# USB_charger.net
KiCad netlist of a schematic drawn in Altium Designer
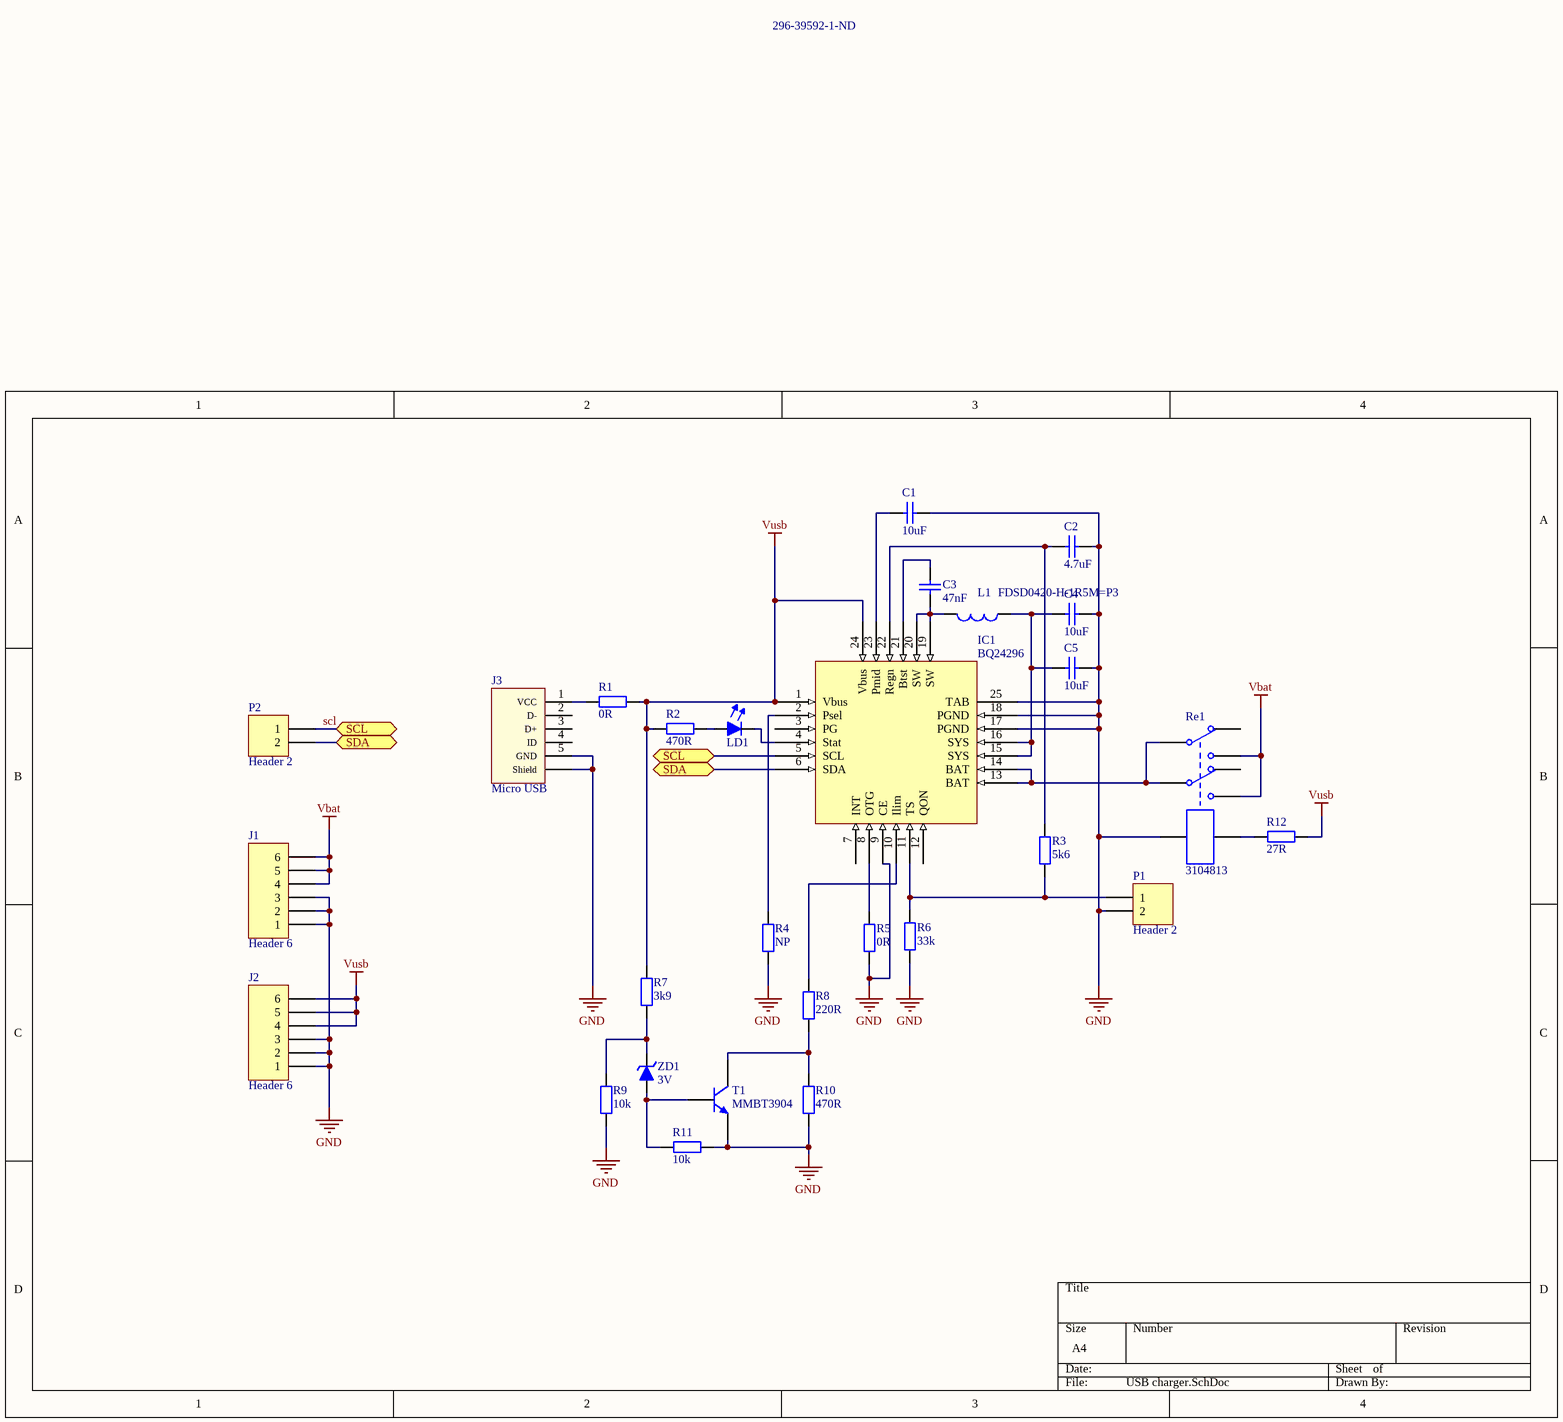
[diagram p0: USB charger.SchDoc]

(export (version "E")
  (design (tool "Eeschema 10.0.6"))
  (components
    (comp (ref "C1")
      (value "10uF")
      (footprint "0805 CAP")
      (description "Capacitor")
      (fields (field (name "VOLTAGE") "10V"))
      (libsource (lib "IKSOR_LIB_main") (part "Capacitor NP"))
    )
    (comp (ref "C2")
      (value "4.7uF")
      (footprint "0805 CAP")
      (description "Capacitor")
      (fields (field (name "VOLTAGE") "10V"))
      (libsource (lib "IKSOR_LIB_main") (part "Capacitor NP"))
    )
    (comp (ref "C3")
      (value "47nF")
      (footprint "0603 cap")
      (description "Capacitor")
      (fields (field (name "VOLTAGE") "10V"))
      (libsource (lib "IKSOR_LIB_main") (part "Capacitor NP"))
    )
    (comp (ref "C4")
      (value "10uF")
      (footprint "0805 CAP")
      (description "Capacitor")
      (fields (field (name "VOLTAGE") "10V"))
      (libsource (lib "IKSOR_LIB_main") (part "Capacitor NP"))
    )
    (comp (ref "C5")
      (value "10uF")
      (footprint "0805 CAP")
      (description "Capacitor")
      (fields (field (name "VOLTAGE") "10V"))
      (libsource (lib "IKSOR_LIB_main") (part "Capacitor NP"))
    )
    (comp (ref "IC1")
      (value "BQ24296")
      (footprint "QFN4x4")
      (description "Battery charger")
      (fields (field (name "SUPPLIER PART NUMBER 1") "296-39592-1-ND"))
      (libsource (lib "IKSOR_LIB_main") (part "BQ24296"))
    )
    (comp (ref "J1")
      (value "Header 6")
      (footprint "HDR1X6")
      (description "Header, 6-Pin")
      (fields (field (name "PUBLISHER") "Altium Limited"))
      (libsource (lib "Miscellaneous Connectors") (part "Header 6"))
    )
    (comp (ref "J2")
      (value "Header 6")
      (footprint "HDR1X6")
      (description "Header, 6-Pin")
      (fields (field (name "PUBLISHER") "Altium Limited"))
      (libsource (lib "Miscellaneous Connectors") (part "Header 6"))
    )
    (comp (ref "J3")
      (value "Micro USB")
      (footprint "629105150521")
      (description "Micro USB 2.0 SMT Type B Horizontal 5 Contacts High Current WR-COM")
      (fields (field (name "PART NUMBER") "629105150521") (field (name "PUBLISHER") "Wurth Elektronik"))
      (libsource (lib "ALTIUM-WR-COM-rev17a") (part "629105150521"))
    )
    (comp (ref "L1")
      (value "FDSD0420-H-1R5M=P3")
      (footprint "FDSD0420-H")
      (description "Single coil")
      (fields (field (name "Comment") "Inductor FDSD0420"))
      (libsource (lib "IKSOR_LIB_main") (part "Inductor"))
    )
    (comp (ref "LD1")
      (value "LED diode")
      (footprint "LED_0603")
      (description "LED")
      (libsource (lib "IKSOR_LIB_main") (part "LED diode"))
    )
    (comp (ref "P1")
      (value "Header 2")
      (footprint "HDR1X2")
      (description "Header, 2-Pin")
      (fields (field (name "PUBLISHER") "Altium Limited"))
      (libsource (lib "") (part "Header 2_1"))
    )
    (comp (ref "P2")
      (value "Header 2")
      (footprint "HDR1X2")
      (description "Header, 2-Pin")
      (fields (field (name "PUBLISHER") "Altium Limited"))
      (libsource (lib "Miscellaneous Connectors") (part "Header 2"))
    )
    (comp (ref "R1")
      (value "0R")
      (footprint "0805 RES")
      (description "Resistor SMD")
      (fields (field (name "Comment") "Resistor generic"))
      (libsource (lib "IKSOR_LIB_main") (part "Resistor"))
    )
    (comp (ref "R2")
      (value "470R")
      (footprint "0603 RES")
      (description "Resistor SMD")
      (fields (field (name "Comment") "Resistor generic"))
      (libsource (lib "IKSOR_LIB_main") (part "Resistor"))
    )
    (comp (ref "R3")
      (value "5k6")
      (footprint "0603 RES")
      (description "Resistor SMD")
      (fields (field (name "Comment") "Resistor generic"))
      (libsource (lib "IKSOR_LIB_main") (part "Resistor"))
    )
    (comp (ref "R4")
      (value "NP")
      (footprint "0603 RES")
      (description "Resistor SMD")
      (fields (field (name "Comment") "Resistor generic"))
      (libsource (lib "IKSOR_LIB_main") (part "Resistor"))
    )
    (comp (ref "R5")
      (value "0R")
      (footprint "0603 RES")
      (description "Resistor SMD")
      (fields (field (name "Comment") "Resistor generic"))
      (libsource (lib "IKSOR_LIB_main") (part "Resistor"))
    )
    (comp (ref "R6")
      (value "33k")
      (footprint "0603 RES")
      (description "Resistor SMD")
      (fields (field (name "Comment") "Resistor generic"))
      (libsource (lib "IKSOR_LIB_main") (part "Resistor"))
    )
    (comp (ref "R7")
      (value "3k9")
      (footprint "0603 RES")
      (description "Resistor SMD")
      (fields (field (name "Comment") "Resistor generic"))
      (libsource (lib "IKSOR_LIB_main") (part "Resistor"))
    )
    (comp (ref "R8")
      (value "220R")
      (footprint "0603 RES")
      (description "Resistor SMD")
      (fields (field (name "Comment") "Resistor generic"))
      (libsource (lib "IKSOR_LIB_main") (part "Resistor"))
    )
    (comp (ref "R9")
      (value "10k")
      (footprint "0603 RES")
      (description "Resistor SMD")
      (fields (field (name "Comment") "Resistor generic"))
      (libsource (lib "IKSOR_LIB_main") (part "Resistor"))
    )
    (comp (ref "R10")
      (value "470R")
      (footprint "0603 RES")
      (description "Resistor SMD")
      (fields (field (name "Comment") "Resistor generic"))
      (libsource (lib "IKSOR_LIB_main") (part "Resistor"))
    )
    (comp (ref "R11")
      (value "10k")
      (footprint "0603 RES")
      (description "Resistor SMD")
      (fields (field (name "Comment") "Resistor generic"))
      (libsource (lib "IKSOR_LIB_main") (part "Resistor"))
    )
    (comp (ref "R12")
      (value "27R")
      (footprint "0603 RES")
      (description "Resistor SMD")
      (fields (field (name "Comment") "Resistor generic"))
      (libsource (lib "IKSOR_LIB_main") (part "Resistor"))
    )
    (comp (ref "Re1")
      (value "Relay dual")
      (footprint "Relay AGQ2004H")
      (description "Farnell 3104813")
      (fields (field (name "SUPPLIER PART NUMBER 1") "3104813"))
      (libsource (lib "IKSOR_LIB_main") (part "Relay dual"))
    )
    (comp (ref "T1") (value "MMBT3904") (footprint "BC857") (libsource (lib "VolkD3D") (part "TR-NPN-PS")))
    (comp (ref "ZD1")
      (value "3V")
      (footprint "SOD323")
      (description "Zener")
      (fields (field (name "Comment") "Diode Zener"))
      (libsource (lib "IKSOR_LIB_main") (part "Diode Zener"))
    )
  )
  (nets
    (net (code "1") (name "/SDA") (class "Default")
      (node (ref "IC1") (pin "6") (pinfunction "SDA_6") (pintype "input"))
      (node (ref "P2") (pin "2") (pinfunction "2_2") (pintype "passive"))
    )
    (net (code "2") (name "/scl") (class "Default")
      (node (ref "IC1") (pin "5") (pinfunction "SCL_5") (pintype "input"))
      (node (ref "P2") (pin "1") (pinfunction "1_1") (pintype "passive"))
    )
    (net (code "3") (name "GND") (class "Default")
      (node (ref "C1") (pin "2") (pinfunction "2_2") (pintype "passive"))
      (node (ref "C2") (pin "1") (pinfunction "1_1") (pintype "passive"))
      (node (ref "C4") (pin "2") (pinfunction "2_2") (pintype "passive"))
      (node (ref "C5") (pin "2") (pinfunction "2_2") (pintype "passive"))
      (node (ref "IC1") (pin "17") (pinfunction "PGND_17") (pintype "input"))
      (node (ref "IC1") (pin "18") (pinfunction "PGND_18") (pintype "input"))
      (node (ref "IC1") (pin "25") (pinfunction "TAB_25") (pintype "passive"))
      (node (ref "IC1") (pin "9") (pinfunction "CE_9") (pintype "input"))
      (node (ref "J1") (pin "1") (pinfunction "1_1") (pintype "passive"))
      (node (ref "J1") (pin "2") (pinfunction "2_2") (pintype "passive"))
      (node (ref "J1") (pin "3") (pinfunction "3_3") (pintype "passive"))
      (node (ref "J2") (pin "1") (pinfunction "1_1") (pintype "passive"))
      (node (ref "J2") (pin "2") (pinfunction "2_2") (pintype "passive"))
      (node (ref "J2") (pin "3") (pinfunction "3_3") (pintype "passive"))
      (node (ref "J3") (pin "5") (pinfunction "GND_5") (pintype "passive"))
      (node (ref "J3") (pin "Shell") (pinfunction "Shield_Shell") (pintype "passive"))
      (node (ref "P1") (pin "2") (pinfunction "2_2") (pintype "passive"))
      (node (ref "R10") (pin "1") (pinfunction "1_1") (pintype "passive"))
      (node (ref "R11") (pin "1") (pinfunction "1_1") (pintype "passive"))
      (node (ref "R4") (pin "1") (pinfunction "1_1") (pintype "passive"))
      (node (ref "R5") (pin "1") (pinfunction "1_1") (pintype "passive"))
      (node (ref "R6") (pin "1") (pinfunction "1_1") (pintype "passive"))
      (node (ref "R9") (pin "2") (pinfunction "2_2") (pintype "passive"))
      (node (ref "Re1") (pin "1") (pinfunction "C1_1") (pintype "passive"))
      (node (ref "T1") (pin "3") (pinfunction "E_3") (pintype "passive"))
    )
    (net (code "4") (name "Net-(C3-Pad1)") (class "Default")
      (node (ref "C3") (pin "1") (pinfunction "1_1") (pintype "passive"))
      (node (ref "IC1") (pin "19") (pinfunction "SW_19") (pintype "input"))
      (node (ref "IC1") (pin "20") (pinfunction "SW_20") (pintype "input"))
      (node (ref "L1") (pin "2") (pinfunction "2_2") (pintype "passive"))
    )
    (net (code "5") (name "Net-(C4-Pad1)") (class "Default")
      (node (ref "C4") (pin "1") (pinfunction "1_1") (pintype "passive"))
      (node (ref "C5") (pin "1") (pinfunction "1_1") (pintype "passive"))
      (node (ref "IC1") (pin "15") (pinfunction "SYS_15") (pintype "input"))
      (node (ref "IC1") (pin "16") (pinfunction "SYS_16") (pintype "input"))
      (node (ref "L1") (pin "1") (pinfunction "1_1") (pintype "passive"))
    )
    (net (code "6") (name "Net-(IC1-Btst)") (class "Default")
      (node (ref "C3") (pin "2") (pinfunction "2_2") (pintype "passive"))
      (node (ref "IC1") (pin "21") (pinfunction "Btst_21") (pintype "input"))
    )
    (net (code "7") (name "Net-(IC1-Ilim)") (class "Default")
      (node (ref "IC1") (pin "10") (pinfunction "Ilim_10") (pintype "input"))
      (node (ref "R8") (pin "2") (pinfunction "2_2") (pintype "passive"))
    )
    (net (code "8") (name "Net-(IC1-OTG)") (class "Default")
      (node (ref "IC1") (pin "8") (pinfunction "OTG_8") (pintype "input"))
      (node (ref "R5") (pin "2") (pinfunction "2_2") (pintype "passive"))
    )
    (net (code "9") (name "Net-(IC1-Pmid)") (class "Default")
      (node (ref "C1") (pin "1") (pinfunction "1_1") (pintype "passive"))
      (node (ref "IC1") (pin "23") (pinfunction "Pmid_23") (pintype "input"))
    )
    (net (code "10") (name "Net-(IC1-Psel)") (class "Default")
      (node (ref "IC1") (pin "2") (pinfunction "Psel_2") (pintype "input"))
      (node (ref "R4") (pin "2") (pinfunction "2_2") (pintype "passive"))
    )
    (net (code "11") (name "Net-(IC1-Regn)") (class "Default")
      (node (ref "C2") (pin "2") (pinfunction "2_2") (pintype "passive"))
      (node (ref "IC1") (pin "22") (pinfunction "Regn_22") (pintype "input"))
      (node (ref "R3") (pin "1") (pinfunction "1_1") (pintype "passive"))
    )
    (net (code "12") (name "Net-(IC1-Stat)") (class "Default")
      (node (ref "IC1") (pin "4") (pinfunction "Stat_4") (pintype "input"))
      (node (ref "LD1") (pin "2") (pinfunction "K_2") (pintype "passive"))
    )
    (net (code "13") (name "Net-(IC1-TS)") (class "Default")
      (node (ref "IC1") (pin "11") (pinfunction "TS_11") (pintype "input"))
      (node (ref "P1") (pin "1") (pinfunction "1_1") (pintype "passive"))
      (node (ref "R3") (pin "2") (pinfunction "2_2") (pintype "passive"))
      (node (ref "R6") (pin "2") (pinfunction "2_2") (pintype "passive"))
    )
    (net (code "14") (name "Net-(J3-VCC)") (class "Default")
      (node (ref "J3") (pin "1") (pinfunction "VCC_1") (pintype "passive"))
      (node (ref "R1") (pin "1") (pinfunction "1_1") (pintype "passive"))
    )
    (net (code "15") (name "Net-(LD1-A1)") (class "Default")
      (node (ref "LD1") (pin "1") (pinfunction "A1_1") (pintype "passive"))
      (node (ref "R2") (pin "1") (pinfunction "1_1") (pintype "passive"))
    )
    (net (code "16") (name "Net-(Re1-C2)") (class "Default")
      (node (ref "R12") (pin "1") (pinfunction "1_1") (pintype "passive"))
      (node (ref "Re1") (pin "2") (pinfunction "C2_2") (pintype "passive"))
    )
    (net (code "17") (name "Net-(Re1-COM1)") (class "Default")
      (node (ref "IC1") (pin "13") (pinfunction "BAT_13") (pintype "input"))
      (node (ref "IC1") (pin "14") (pinfunction "BAT_14") (pintype "input"))
      (node (ref "Re1") (pin "3") (pinfunction "COM1_3") (pintype "passive"))
      (node (ref "Re1") (pin "6") (pinfunction "COM2_6") (pintype "passive"))
    )
    (net (code "18") (name "Net-(T1-B)") (class "Default")
      (node (ref "R11") (pin "2") (pinfunction "2_2") (pintype "passive"))
      (node (ref "T1") (pin "1") (pinfunction "B_1") (pintype "passive"))
      (node (ref "ZD1") (pin "1") (pinfunction "A_1") (pintype "passive"))
    )
    (net (code "19") (name "Net-(T1-C)") (class "Default")
      (node (ref "R10") (pin "2") (pinfunction "2_2") (pintype "passive"))
      (node (ref "R8") (pin "1") (pinfunction "1_1") (pintype "passive"))
      (node (ref "T1") (pin "2") (pinfunction "C_2") (pintype "passive"))
    )
    (net (code "20") (name "Net-(ZD1-K)") (class "Default")
      (node (ref "R7") (pin "2") (pinfunction "2_2") (pintype "passive"))
      (node (ref "R9") (pin "1") (pinfunction "1_1") (pintype "passive"))
      (node (ref "ZD1") (pin "2") (pinfunction "K_2") (pintype "passive"))
    )
    (net (code "21") (name "Vbat") (class "Default")
      (node (ref "J1") (pin "4") (pinfunction "4_4") (pintype "passive"))
      (node (ref "J1") (pin "5") (pinfunction "5_5") (pintype "passive"))
      (node (ref "J1") (pin "6") (pinfunction "6_6") (pintype "passive"))
      (node (ref "Re1") (pin "4") (pinfunction "NO1_4") (pintype "passive"))
      (node (ref "Re1") (pin "7") (pinfunction "NO2_7") (pintype "passive"))
    )
    (net (code "22") (name "Vusb") (class "Default")
      (node (ref "IC1") (pin "1") (pinfunction "Vbus_1") (pintype "input"))
      (node (ref "IC1") (pin "24") (pinfunction "Vbus_24") (pintype "input"))
      (node (ref "J2") (pin "4") (pinfunction "4_4") (pintype "passive"))
      (node (ref "J2") (pin "5") (pinfunction "5_5") (pintype "passive"))
      (node (ref "J2") (pin "6") (pinfunction "6_6") (pintype "passive"))
      (node (ref "R1") (pin "2") (pinfunction "2_2") (pintype "passive"))
      (node (ref "R12") (pin "2") (pinfunction "2_2") (pintype "passive"))
      (node (ref "R2") (pin "2") (pinfunction "2_2") (pintype "passive"))
      (node (ref "R7") (pin "1") (pinfunction "1_1") (pintype "passive"))
    )
    (net (code "23") (name "unconnected-(IC1-INT-Pad7)") (class "Default")
      (node (ref "IC1") (pin "7") (pinfunction "INT_7") (pintype "input"))
    )
    (net (code "24") (name "unconnected-(IC1-PG-Pad3)") (class "Default")
      (node (ref "IC1") (pin "3") (pinfunction "PG_3") (pintype "input"))
    )
    (net (code "25") (name "unconnected-(IC1-QON-Pad12)") (class "Default")
      (node (ref "IC1") (pin "12") (pinfunction "QON_12") (pintype "input"))
    )
    (net (code "26") (name "unconnected-(J3-D+-Pad3)") (class "Default")
      (node (ref "J3") (pin "3") (pinfunction "D+_3") (pintype "passive"))
    )
    (net (code "27") (name "unconnected-(J3-D--Pad2)") (class "Default")
      (node (ref "J3") (pin "2") (pinfunction "D-_2") (pintype "passive"))
    )
    (net (code "28") (name "unconnected-(J3-ID-Pad4)") (class "Default")
      (node (ref "J3") (pin "4") (pinfunction "ID_4") (pintype "passive"))
    )
    (net (code "29") (name "unconnected-(Re1-NC1-Pad5)") (class "Default")
      (node (ref "Re1") (pin "5") (pinfunction "NC1_5") (pintype "passive"))
    )
    (net (code "30") (name "unconnected-(Re1-NC2-Pad8)") (class "Default")
      (node (ref "Re1") (pin "8") (pinfunction "NC2_8") (pintype "passive"))
    )
  )
)
